# Gate_Control.net
KiCad netlist of a schematic drawn in Altium Designer
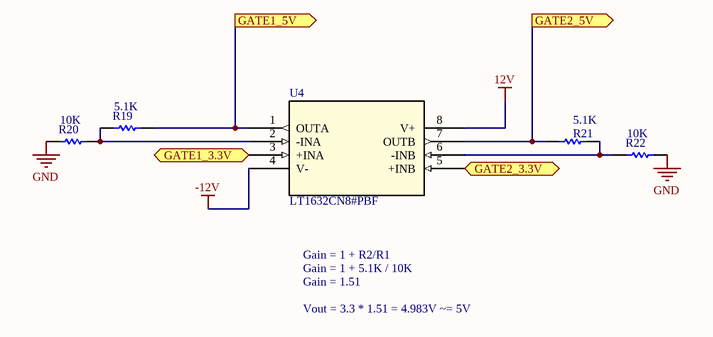
[diagram p0: Gate_Control.SchDoc]

(export (version "E")
  (design (tool "Eeschema 10.0.6"))
  (components
    (comp (ref "R19")
      (value "5.1K")
      (footprint "AXIAL-0.3")
      (description "Resistor")
      (fields (field (name "Comment") "Res1") (field (name "PUBLISHER") "Altium Limited"))
      (libsource (lib "Miscellaneous Devices") (part "Res1"))
    )
    (comp (ref "R20")
      (value "10K")
      (footprint "AXIAL-0.3")
      (description "Resistor")
      (fields (field (name "Comment") "Res1") (field (name "PUBLISHER") "Altium Limited"))
      (libsource (lib "Miscellaneous Devices") (part "Res1"))
    )
    (comp (ref "R21")
      (value "5.1K")
      (footprint "AXIAL-0.3")
      (description "Resistor")
      (fields (field (name "Comment") "Res1") (field (name "PUBLISHER") "Altium Limited"))
      (libsource (lib "Miscellaneous Devices") (part "Res1"))
    )
    (comp (ref "R22")
      (value "10K")
      (footprint "AXIAL-0.3")
      (description "Resistor")
      (fields (field (name "Comment") "Res1") (field (name "PUBLISHER") "Altium Limited"))
      (libsource (lib "Miscellaneous Devices") (part "Res1"))
    )
    (comp (ref "U4")
      (value "LT1632CN8#PBF")
      (footprint "PDIP-8_N")
      (description "Imported")
      (fields
        (field (name "DIGIKEYPARTNUMBER") "LT1632CN8-ND")
        (field (name "COPYRIGHT") "Copyright (C) 2015 Accelerated Designs. All rights reserved")
      )
      (libsource (lib "lt1632") (part "LT1632CN8#PBF"))
    )
  )
  (nets
    (net (code "1") (name "-12V") (class "Default")
      (node (ref "U4") (pin "4") (pinfunction "V-_4") (pintype "power_in"))
    )
    (net (code "2") (name "/GATE1_3.3V") (class "Default")
      (node (ref "U4") (pin "3") (pinfunction "+INA_3") (pintype "input"))
    )
    (net (code "3") (name "/GATE1_5V") (class "Default")
      (node (ref "R19") (pin "2") (pinfunction "2_2") (pintype "passive"))
      (node (ref "U4") (pin "1") (pinfunction "OUTA_1") (pintype "output"))
    )
    (net (code "4") (name "/GATE2_3.3V") (class "Default")
      (node (ref "U4") (pin "5") (pinfunction "+INB_5") (pintype "input"))
    )
    (net (code "5") (name "/GATE2_5V") (class "Default")
      (node (ref "R21") (pin "1") (pinfunction "1_1") (pintype "passive"))
      (node (ref "U4") (pin "7") (pinfunction "OUTB_7") (pintype "output"))
    )
    (net (code "6") (name "12V") (class "Default")
      (node (ref "U4") (pin "8") (pinfunction "V+_8") (pintype "power_in"))
    )
    (net (code "7") (name "GND") (class "Default")
      (node (ref "R20") (pin "1") (pinfunction "1_1") (pintype "passive"))
      (node (ref "R22") (pin "2") (pinfunction "2_2") (pintype "passive"))
    )
    (net (code "8") (name "Net-(U4--INA)") (class "Default")
      (node (ref "R19") (pin "1") (pinfunction "1_1") (pintype "passive"))
      (node (ref "R20") (pin "2") (pinfunction "2_2") (pintype "passive"))
      (node (ref "U4") (pin "2") (pinfunction "-INA_2") (pintype "input"))
    )
    (net (code "9") (name "Net-(U4--INB)") (class "Default")
      (node (ref "R21") (pin "2") (pinfunction "2_2") (pintype "passive"))
      (node (ref "R22") (pin "1") (pinfunction "1_1") (pintype "passive"))
      (node (ref "U4") (pin "6") (pinfunction "-INB_6") (pintype "input"))
    )
  )
)
